# Node_Sensor_Lora_Sche.net
KiCad netlist of a schematic drawn in Altium Designer
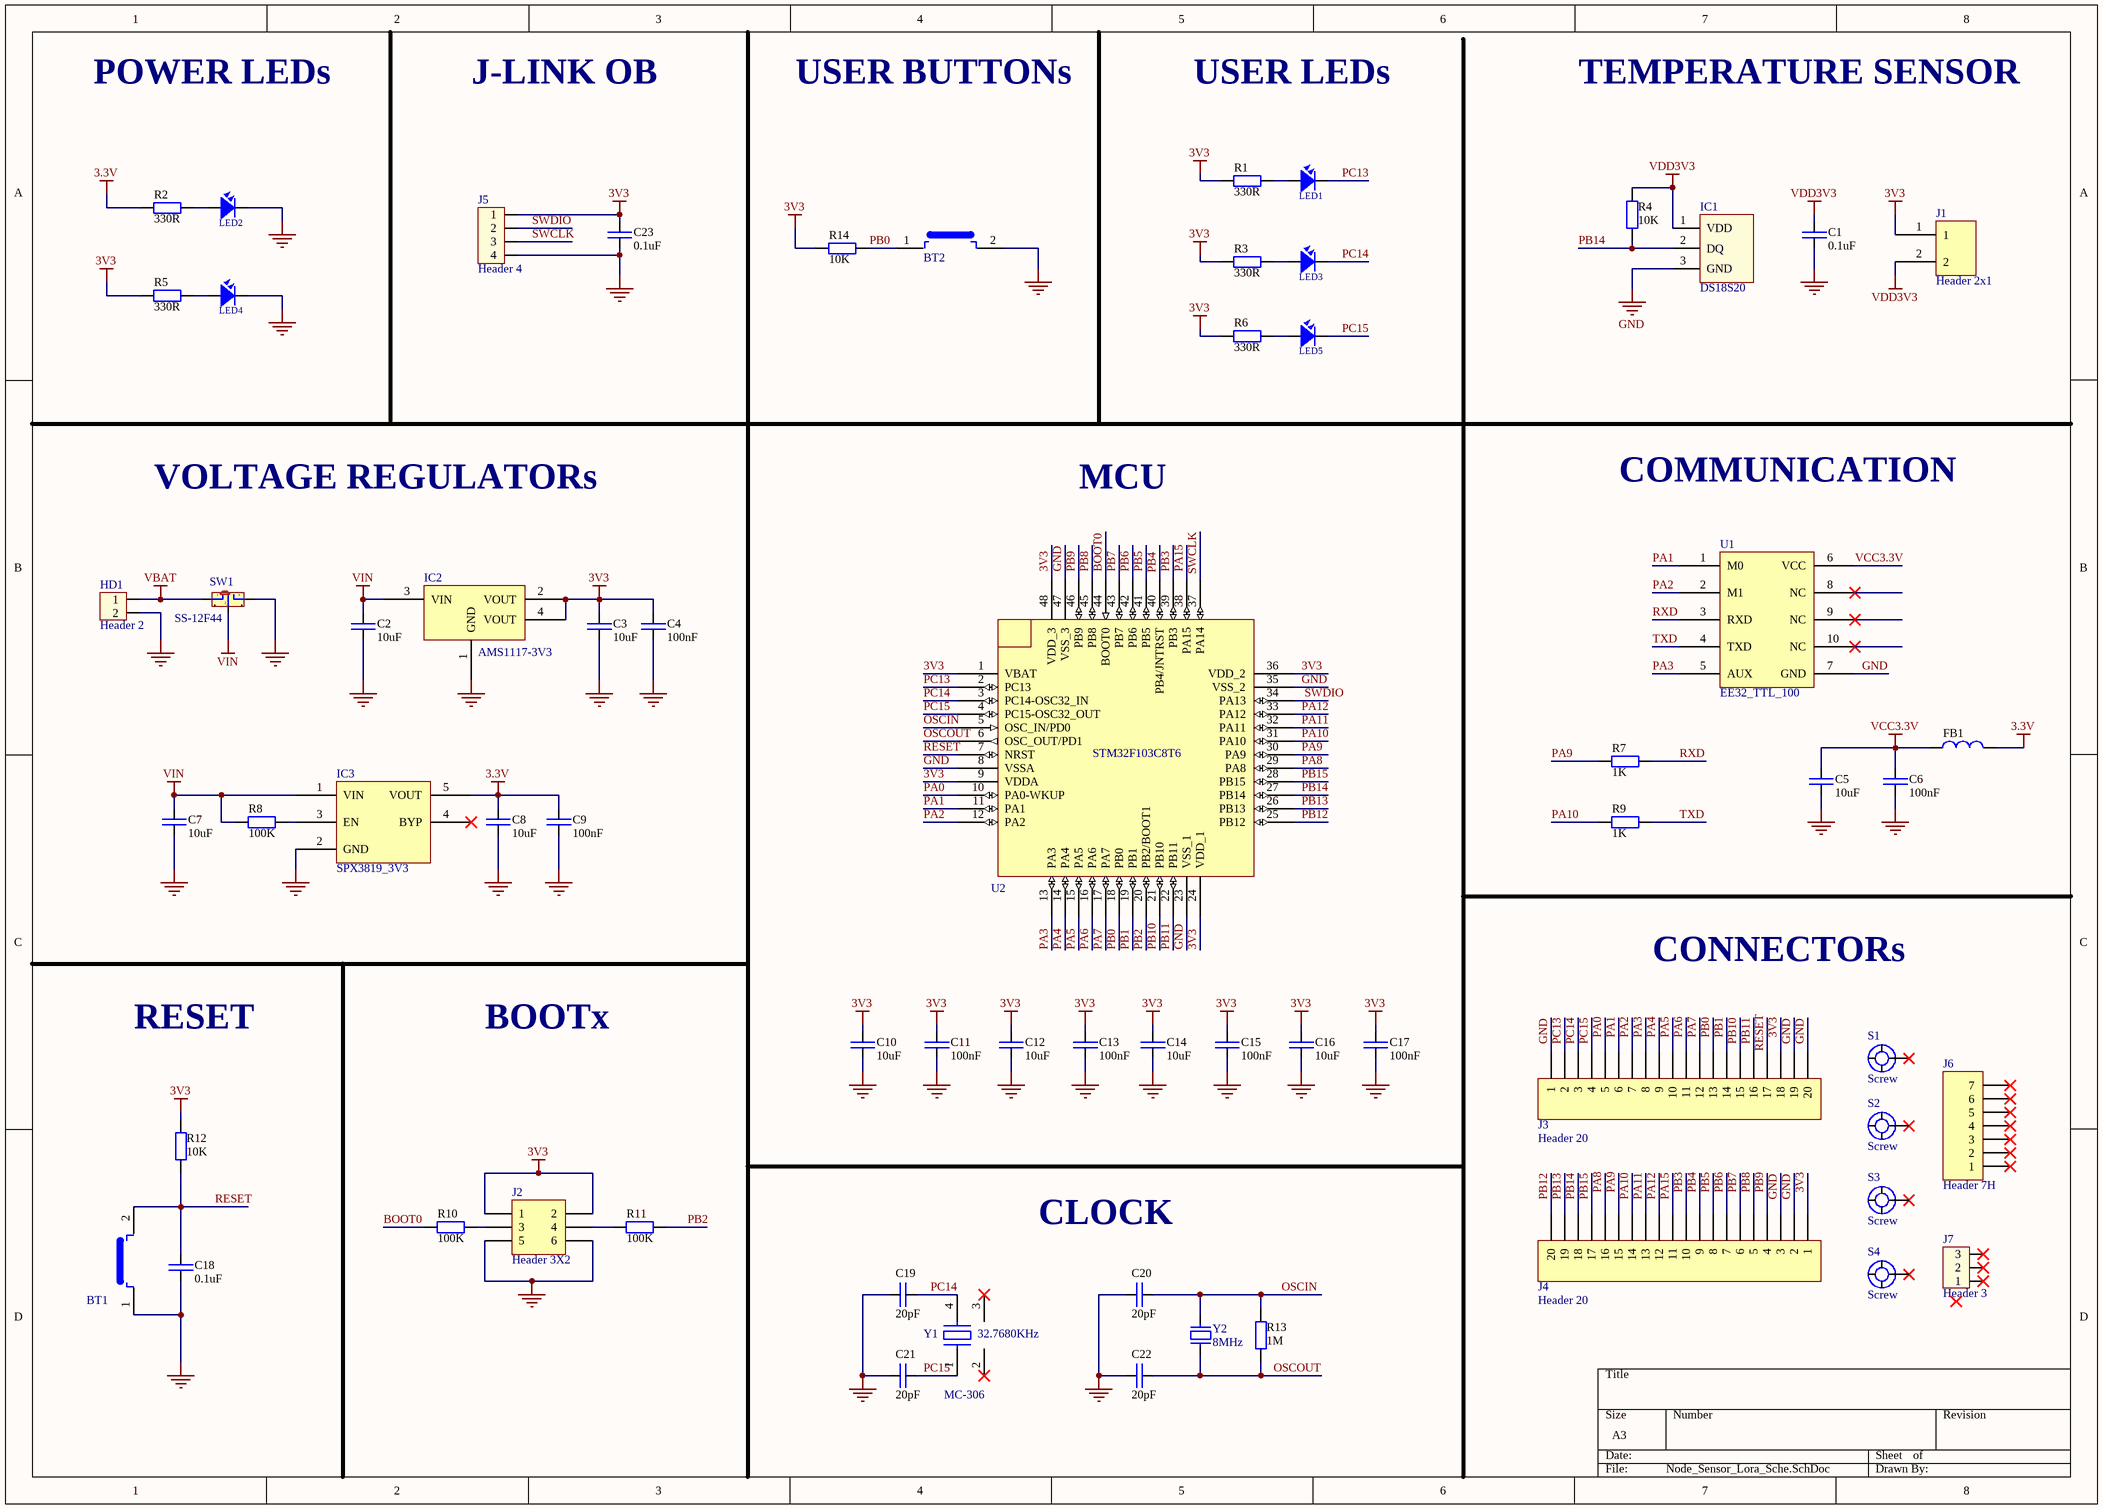
[diagram p0: Node_Sensor_Lora_Sche.SchDoc]

(export (version "E")
  (design (tool "Eeschema 10.0.6"))
  (components
    (comp (ref "BT1") (value "~") (footprint "SW4") (libsource (lib "my_Library") (part "BUTTON")))
    (comp (ref "BT2") (value "BT") (footprint "SW4") (libsource (lib "my_Library") (part "BUTTON")))
    (comp (ref "C1")
      (value "0.1uF")
      (footprint "CAPC2012X135N")
      (description "Capacitor SMD Cer 1.8nF 10% 50V X7R 0805")
      (fields (field (name "TOLERANCE") "±10%") (field (name "Comment") "approved sub OK"))
      (libsource (lib "my_Library") (part "CAP C_0805"))
    )
    (comp (ref "C2")
      (value "10uF")
      (footprint "CAPC2012X135N")
      (description "Capacitor SMD Cer 1.8nF 10% 50V X7R 0805")
      (fields (field (name "TOLERANCE") "±10%") (field (name "Comment") "approved sub OK"))
      (libsource (lib "my_Library") (part "CAP C_0805"))
    )
    (comp (ref "C3")
      (value "10uF")
      (footprint "CAPC2012X135N")
      (description "Capacitor SMD Cer 1.8nF 10% 50V X7R 0805")
      (fields (field (name "TOLERANCE") "±10%") (field (name "Comment") "approved sub OK"))
      (libsource (lib "my_Library") (part "CAP C_0805"))
    )
    (comp (ref "C4")
      (value "100nF")
      (footprint "CAPC2012X135N")
      (description "Capacitor SMD Cer 1.8nF 10% 50V X7R 0805")
      (fields (field (name "TOLERANCE") "±10%") (field (name "Comment") "approved sub OK"))
      (libsource (lib "my_Library") (part "CAP C_0805"))
    )
    (comp (ref "C5")
      (value "10uF")
      (footprint "CAPC2012X135N")
      (description "Capacitor SMD Cer 1.8nF 10% 50V X7R 0805")
      (fields (field (name "TOLERANCE") "±10%") (field (name "Comment") "approved sub OK"))
      (libsource (lib "my_Library") (part "CAP C_0805"))
    )
    (comp (ref "C6")
      (value "100nF")
      (footprint "CAPC2012X135N")
      (description "Capacitor SMD Cer 1.8nF 10% 50V X7R 0805")
      (fields (field (name "TOLERANCE") "±10%") (field (name "Comment") "approved sub OK"))
      (libsource (lib "my_Library") (part "CAP C_0805"))
    )
    (comp (ref "C7")
      (value "10uF")
      (footprint "CAPC2012X135N")
      (description "Capacitor SMD Cer 1.8nF 10% 50V X7R 0805")
      (fields (field (name "TOLERANCE") "±10%") (field (name "Comment") "approved sub OK"))
      (libsource (lib "my_Library") (part "CAP C_0805"))
    )
    (comp (ref "C8")
      (value "10uF")
      (footprint "CAPC2012X135N")
      (description "Capacitor SMD Cer 1.8nF 10% 50V X7R 0805")
      (fields (field (name "TOLERANCE") "±10%") (field (name "Comment") "approved sub OK"))
      (libsource (lib "my_Library") (part "CAP C_0805"))
    )
    (comp (ref "C9")
      (value "100nF")
      (footprint "CAPC2012X135N")
      (description "Capacitor SMD Cer 1.8nF 10% 50V X7R 0805")
      (fields (field (name "TOLERANCE") "±10%") (field (name "Comment") "approved sub OK"))
      (libsource (lib "my_Library") (part "CAP C_0805"))
    )
    (comp (ref "C10")
      (value "10uF")
      (footprint "CAPC2012X135N")
      (description "Capacitor SMD Cer 1.8nF 10% 50V X7R 0805")
      (fields (field (name "TOLERANCE") "±10%") (field (name "Comment") "approved sub OK"))
      (libsource (lib "my_Library") (part "CAP C_0805"))
    )
    (comp (ref "C11")
      (value "100nF")
      (footprint "CAPC2012X135N")
      (description "Capacitor SMD Cer 1.8nF 10% 50V X7R 0805")
      (fields (field (name "TOLERANCE") "±10%") (field (name "Comment") "approved sub OK"))
      (libsource (lib "my_Library") (part "CAP C_0805"))
    )
    (comp (ref "C12")
      (value "10uF")
      (footprint "CAPC2012X135N")
      (description "Capacitor SMD Cer 1.8nF 10% 50V X7R 0805")
      (fields (field (name "TOLERANCE") "±10%") (field (name "Comment") "approved sub OK"))
      (libsource (lib "my_Library") (part "CAP C_0805"))
    )
    (comp (ref "C13")
      (value "100nF")
      (footprint "CAPC2012X135N")
      (description "Capacitor SMD Cer 1.8nF 10% 50V X7R 0805")
      (fields (field (name "TOLERANCE") "±10%") (field (name "Comment") "approved sub OK"))
      (libsource (lib "my_Library") (part "CAP C_0805"))
    )
    (comp (ref "C14")
      (value "10uF")
      (footprint "CAPC2012X135N")
      (description "Capacitor SMD Cer 1.8nF 10% 50V X7R 0805")
      (fields (field (name "TOLERANCE") "±10%") (field (name "Comment") "approved sub OK"))
      (libsource (lib "my_Library") (part "CAP C_0805"))
    )
    (comp (ref "C15")
      (value "100nF")
      (footprint "CAPC2012X135N")
      (description "Capacitor SMD Cer 1.8nF 10% 50V X7R 0805")
      (fields (field (name "TOLERANCE") "±10%") (field (name "Comment") "approved sub OK"))
      (libsource (lib "my_Library") (part "CAP C_0805"))
    )
    (comp (ref "C16")
      (value "10uF")
      (footprint "CAPC2012X135N")
      (description "Capacitor SMD Cer 1.8nF 10% 50V X7R 0805")
      (fields (field (name "TOLERANCE") "±10%") (field (name "Comment") "approved sub OK"))
      (libsource (lib "my_Library") (part "CAP C_0805"))
    )
    (comp (ref "C17")
      (value "100nF")
      (footprint "CAPC2012X135N")
      (description "Capacitor SMD Cer 1.8nF 10% 50V X7R 0805")
      (fields (field (name "TOLERANCE") "±10%") (field (name "Comment") "approved sub OK"))
      (libsource (lib "my_Library") (part "CAP C_0805"))
    )
    (comp (ref "C18")
      (value "0.1uF")
      (footprint "CAPC2012X135N")
      (description "Capacitor SMD Cer 1.8nF 10% 50V X7R 0805")
      (fields (field (name "TOLERANCE") "±10%") (field (name "Comment") "approved sub OK"))
      (libsource (lib "my_Library") (part "CAP C_0805"))
    )
    (comp (ref "C19")
      (value "20pF")
      (footprint "CAPC2012X135N")
      (description "Capacitor SMD Cer 1.8nF 10% 50V X7R 0805")
      (fields (field (name "TOLERANCE") "±10%") (field (name "Comment") "approved sub OK"))
      (libsource (lib "my_Library") (part "CAP C_0805"))
    )
    (comp (ref "C20")
      (value "20pF")
      (footprint "CAPC2012X135N")
      (description "Capacitor SMD Cer 1.8nF 10% 50V X7R 0805")
      (fields (field (name "TOLERANCE") "±10%") (field (name "Comment") "approved sub OK"))
      (libsource (lib "my_Library") (part "CAP C_0805"))
    )
    (comp (ref "C21")
      (value "20pF")
      (footprint "CAPC2012X135N")
      (description "Capacitor SMD Cer 1.8nF 10% 50V X7R 0805")
      (fields (field (name "TOLERANCE") "±10%") (field (name "Comment") "approved sub OK"))
      (libsource (lib "my_Library") (part "CAP C_0805"))
    )
    (comp (ref "C22")
      (value "20pF")
      (footprint "CAPC2012X135N")
      (description "Capacitor SMD Cer 1.8nF 10% 50V X7R 0805")
      (fields (field (name "TOLERANCE") "±10%") (field (name "Comment") "approved sub OK"))
      (libsource (lib "my_Library") (part "CAP C_0805"))
    )
    (comp (ref "C23")
      (value "0.1uF")
      (footprint "CAPC2012X135N")
      (description "Capacitor SMD Cer 1.8nF 10% 50V X7R 0805")
      (fields (field (name "TOLERANCE") "±10%") (field (name "Comment") "approved sub OK"))
      (libsource (lib "my_Library") (part "CAP C_0805"))
    )
    (comp (ref "FB1")
      (value "2K2 @ 100 MHz")
      (footprint "FBC2012N")
      (description "Ferrite bead 2.2K Ohm at 100 MHz 200mA 0805 SMD")
      (libsource (lib "my_Library") (part "FERRITE_2K2-100MHz_0805"))
    )
    (comp (ref "HD1")
      (value "Header 2")
      (footprint "HED2")
      (description "Header 2 (Green)")
      (libsource (lib "my_Library") (part "Header 2"))
    )
    (comp (ref "IC1")
      (value "DS18S20")
      (footprint "DS18S20")
      (description "High Precision  1-Wire® Digital Thermometer")
      (libsource (lib "my_Library") (part "DS18S20"))
    )
    (comp (ref "IC2")
      (value "AMS1117-3V3")
      (footprint "SOT223")
      (description "SOT223, Fixed Voltage")
      (libsource (lib "my_Library") (part "AMS1117"))
    )
    (comp (ref "IC3")
      (value "SPX3819_3V3")
      (footprint "SOT23-5")
      (libsource (lib "my_Library") (part "SPX3819"))
    )
    (comp (ref "J1")
      (value "Header 2x1")
      (footprint "HDR_2x1")
      (libsource (lib "my_Library") (part "Header_2pins"))
    )
    (comp (ref "J2")
      (value "Header 3X2")
      (footprint "HDR2X3")
      (description "Header, 3-Pin, Dual row")
      (fields (field (name "PUBLISHER") "Altium Limited"))
      (libsource (lib "my_Library") (part "Header 3X2"))
    )
    (comp (ref "J3")
      (value "Header 20")
      (footprint "HDR1X20")
      (description "Header, 20-Pin")
      (fields (field (name "PUBLISHER") "Altium Limited"))
      (libsource (lib "my_Library") (part "Header 20"))
    )
    (comp (ref "J4")
      (value "Header 20")
      (footprint "HDR1X20")
      (description "Header, 20-Pin")
      (fields (field (name "PUBLISHER") "Altium Limited"))
      (libsource (lib "") (part "Header 20_1"))
    )
    (comp (ref "J5")
      (value "Header 4")
      (footprint "HDR _4PINS")
      (description "Header 4 (Green)")
      (libsource (lib "my_Library") (part "Header 4"))
    )
    (comp (ref "J6")
      (value "Header 7H")
      (footprint "CON7")
      (description "Header, 7-Pin, Right Angle")
      (fields (field (name "PUBLISHER") "Altium Limited"))
      (libsource (lib "my_Library") (part "Header 7H"))
    )
    (comp (ref "J7")
      (value "Header 3")
      (footprint "HED3")
      (description "Header 3 (Green)")
      (libsource (lib "my_Library") (part "Header 3"))
    )
    (comp (ref "LED1")
      (value "LED SMD")
      (footprint "SM-LED-0805-Blue")
      (libsource (lib "my_Library") (part "LED SMD 0805"))
    )
    (comp (ref "LED2")
      (value "LED SMD")
      (footprint "SM-LED-0805-Blue")
      (libsource (lib "my_Library") (part "LED SMD 0805"))
    )
    (comp (ref "LED3")
      (value "LED SMD")
      (footprint "SM-LED-0805-Blue")
      (libsource (lib "my_Library") (part "LED SMD 0805"))
    )
    (comp (ref "LED4")
      (value "LED SMD")
      (footprint "SM-LED-0805-Blue")
      (libsource (lib "my_Library") (part "LED SMD 0805"))
    )
    (comp (ref "LED5")
      (value "LED SMD")
      (footprint "SM-LED-0805-Blue")
      (libsource (lib "my_Library") (part "LED SMD 0805"))
    )
    (comp (ref "R1")
      (value "330R")
      (footprint "RESC2012N_ZERO")
      (description "Resistor SMD chip 0.0 Ohm 0.125W 0805")
      (fields (field (name "Comment") "100R"))
      (libsource (lib "my_Library") (part "RES_0805"))
    )
    (comp (ref "R2")
      (value "330R")
      (footprint "RESC2012N_ZERO")
      (description "Resistor SMD chip 0.0 Ohm 0.125W 0805")
      (libsource (lib "my_Library") (part "RES_0805"))
    )
    (comp (ref "R3")
      (value "330R")
      (footprint "RESC2012N_ZERO")
      (description "Resistor SMD chip 0.0 Ohm 0.125W 0805")
      (fields (field (name "Comment") "100R"))
      (libsource (lib "my_Library") (part "RES_0805"))
    )
    (comp (ref "R4")
      (value "10K")
      (footprint "RESC2012N_ZERO")
      (description "Resistor SMD chip 0.0 Ohm 0.125W 0805")
      (fields (field (name "Comment") "100R"))
      (libsource (lib "") (part "RES_0805_1"))
    )
    (comp (ref "R5")
      (value "330R")
      (footprint "RESC2012N_ZERO")
      (description "Resistor SMD chip 0.0 Ohm 0.125W 0805")
      (fields (field (name "Comment") "100R"))
      (libsource (lib "my_Library") (part "RES_0805"))
    )
    (comp (ref "R6")
      (value "330R")
      (footprint "RESC2012N_ZERO")
      (description "Resistor SMD chip 0.0 Ohm 0.125W 0805")
      (fields (field (name "Comment") "100R"))
      (libsource (lib "my_Library") (part "RES_0805"))
    )
    (comp (ref "R7")
      (value "1K")
      (footprint "RESC2012N_ZERO")
      (description "Resistor SMD chip 0.0 Ohm 0.125W 0805")
      (fields (field (name "Comment") "100R"))
      (libsource (lib "my_Library") (part "RES_0805"))
    )
    (comp (ref "R8")
      (value "100K")
      (footprint "RESC2012N_ZERO")
      (description "Resistor SMD chip 0.0 Ohm 0.125W 0805")
      (fields (field (name "Comment") "100R"))
      (libsource (lib "my_Library") (part "RES_0805"))
    )
    (comp (ref "R9")
      (value "1K")
      (footprint "RESC2012N_ZERO")
      (description "Resistor SMD chip 0.0 Ohm 0.125W 0805")
      (fields (field (name "Comment") "100R"))
      (libsource (lib "my_Library") (part "RES_0805"))
    )
    (comp (ref "R10")
      (value "100K")
      (footprint "RESC2012N_ZERO")
      (description "Resistor SMD chip 0.0 Ohm 0.125W 0805")
      (fields (field (name "Comment") "100R"))
      (libsource (lib "my_Library") (part "RES_0805"))
    )
    (comp (ref "R11")
      (value "100K")
      (footprint "RESC2012N_ZERO")
      (description "Resistor SMD chip 0.0 Ohm 0.125W 0805")
      (fields (field (name "Comment") "100R"))
      (libsource (lib "my_Library") (part "RES_0805"))
    )
    (comp (ref "R12")
      (value "10K")
      (footprint "RESC2012N_ZERO")
      (description "Resistor SMD chip 0.0 Ohm 0.125W 0805")
      (fields (field (name "Comment") "100R"))
      (libsource (lib "") (part "RES_0805_2"))
    )
    (comp (ref "R13")
      (value "1M")
      (footprint "RESC2012N_ZERO")
      (description "Resistor SMD chip 0.0 Ohm 0.125W 0805")
      (fields (field (name "Comment") "100R"))
      (libsource (lib "") (part "RES_0805_2"))
    )
    (comp (ref "R14")
      (value "10K")
      (footprint "RESC2012N_ZERO")
      (description "Resistor SMD chip 0.0 Ohm 0.125W 0805")
      (fields (field (name "Comment") "100R"))
      (libsource (lib "my_Library") (part "RES_0805"))
    )
    (comp (ref "S1") (value "Screw") (footprint "Screw 3 small") (libsource (lib "lpson") (part "Screw")))
    (comp (ref "S2") (value "Screw") (footprint "Screw 3 small") (libsource (lib "lpson") (part "Screw")))
    (comp (ref "S3") (value "Screw") (footprint "Screw 3 small") (libsource (lib "lpson") (part "Screw")))
    (comp (ref "S4") (value "Screw") (footprint "Screw 3 small") (libsource (lib "lpson") (part "Screw")))
    (comp (ref "SW1")
      (value "SS-12F44")
      (footprint "SW102")
      (description "Switch 102 on Broad")
      (libsource (lib "my_Library") (part "SW102A"))
    )
    (comp (ref "U1")
      (value "EE32_TTL_100")
      (footprint "E32_TTL_100")
      (libsource (lib "my_Library") (part "Module Lora E32_TTL_100"))
    )
    (comp (ref "U2")
      (value "STM32F103C8T6")
      (footprint "STM32_LQPF48")
      (description "STM32 ARM-based 32-bit MCU with 64 Kbytes Flash, 48-pin LQFP, Industrial Temperature")
      (fields (field (name "PUBLISHER") "Altium Limited"))
      (libsource (lib "my_Library") (part "STM32F103xx_LQFP48"))
    )
    (comp (ref "Y1")
      (value "32.7680KHz")
      (footprint "Epson_MC-306_32.7680K-A0-ROHS_0")
      (description "CRYSTAL 32.7680KHZ 12.5PF SMD")
      (fields
        (field (name "PART NUMBER") "MC-306")
        (field (name "MANUFACTURER") "Epson")
        (field (name "MOUSER PART NUMBER") "732-MC30632.7680KA0R")
      )
      (libsource (lib "Crys_Epson_MC-306_32.7680K-A0-ROHS_eec") (part "Crys_Epson_MC-306_32.7680K-A0-ROHS_eec"))
    )
    (comp (ref "Y2")
      (value "8MHz")
      (footprint "CRYSTAL")
      (description "Crystal For all Crystal 2pin.")
      (libsource (lib "my_Library") (part "CRYSTAL"))
    )
  )
  (nets
    (net (code "1") (name "/BOOT0") (class "Default")
      (node (ref "R10") (pin "1") (pinfunction "1_1") (pintype "passive"))
      (node (ref "U2") (pin "44") (pinfunction "BOOT0_44") (pintype "input"))
    )
    (net (code "2") (name "/OSCIN") (class "Default")
      (node (ref "C20") (pin "2") (pintype "passive"))
      (node (ref "R13") (pin "1") (pinfunction "1_1") (pintype "passive"))
      (node (ref "U2") (pin "5") (pinfunction "OSC_IN/PD0_5") (pintype "input"))
      (node (ref "Y2") (pin "2") (pinfunction "2_2") (pintype "passive"))
    )
    (net (code "3") (name "/OSCOUT") (class "Default")
      (node (ref "C22") (pin "2") (pintype "passive"))
      (node (ref "R13") (pin "2") (pinfunction "2_2") (pintype "passive"))
      (node (ref "U2") (pin "6") (pinfunction "OSC_OUT/PD1_6") (pintype "output"))
      (node (ref "Y2") (pin "1") (pinfunction "1_1") (pintype "passive"))
    )
    (net (code "4") (name "/PA0") (class "Default")
      (node (ref "J3") (pin "5") (pinfunction "5_5") (pintype "passive"))
      (node (ref "U2") (pin "10") (pinfunction "PA0-WKUP_10") (pintype "bidirectional"))
    )
    (net (code "5") (name "/PA1") (class "Default")
      (node (ref "J3") (pin "6") (pinfunction "6_6") (pintype "passive"))
      (node (ref "U1") (pin "1") (pinfunction "M0_1") (pintype "passive"))
      (node (ref "U2") (pin "11") (pinfunction "PA1_11") (pintype "bidirectional"))
    )
    (net (code "6") (name "/PA2") (class "Default")
      (node (ref "J3") (pin "7") (pinfunction "7_7") (pintype "passive"))
      (node (ref "U1") (pin "2") (pinfunction "M1_2") (pintype "passive"))
      (node (ref "U2") (pin "12") (pinfunction "PA2_12") (pintype "bidirectional"))
    )
    (net (code "7") (name "/PA3") (class "Default")
      (node (ref "J3") (pin "8") (pinfunction "8_8") (pintype "passive"))
      (node (ref "U1") (pin "5") (pinfunction "AUX_5") (pintype "passive"))
      (node (ref "U2") (pin "13") (pinfunction "PA3_13") (pintype "bidirectional"))
    )
    (net (code "8") (name "/PA4") (class "Default")
      (node (ref "J3") (pin "9") (pinfunction "9_9") (pintype "passive"))
      (node (ref "U2") (pin "14") (pinfunction "PA4_14") (pintype "bidirectional"))
    )
    (net (code "9") (name "/PA5") (class "Default")
      (node (ref "J3") (pin "10") (pinfunction "10_10") (pintype "passive"))
      (node (ref "U2") (pin "15") (pinfunction "PA5_15") (pintype "bidirectional"))
    )
    (net (code "10") (name "/PA6") (class "Default")
      (node (ref "J3") (pin "11") (pinfunction "11_11") (pintype "passive"))
      (node (ref "U2") (pin "16") (pinfunction "PA6_16") (pintype "bidirectional"))
    )
    (net (code "11") (name "/PA7") (class "Default")
      (node (ref "J3") (pin "12") (pinfunction "12_12") (pintype "passive"))
      (node (ref "U2") (pin "17") (pinfunction "PA7_17") (pintype "bidirectional"))
    )
    (net (code "12") (name "/PA8") (class "Default")
      (node (ref "J4") (pin "16") (pinfunction "16_16") (pintype "passive"))
      (node (ref "U2") (pin "29") (pinfunction "PA8_29") (pintype "bidirectional"))
    )
    (net (code "13") (name "/PA9") (class "Default")
      (node (ref "J4") (pin "15") (pinfunction "15_15") (pintype "passive"))
      (node (ref "R7") (pin "1") (pinfunction "1_1") (pintype "passive"))
      (node (ref "U2") (pin "30") (pinfunction "PA9_30") (pintype "bidirectional"))
    )
    (net (code "14") (name "/PA10") (class "Default")
      (node (ref "J4") (pin "14") (pinfunction "14_14") (pintype "passive"))
      (node (ref "R9") (pin "1") (pinfunction "1_1") (pintype "passive"))
      (node (ref "U2") (pin "31") (pinfunction "PA10_31") (pintype "bidirectional"))
    )
    (net (code "15") (name "/PA11") (class "Default")
      (node (ref "J4") (pin "13") (pinfunction "13_13") (pintype "passive"))
      (node (ref "U2") (pin "32") (pinfunction "PA11_32") (pintype "bidirectional"))
    )
    (net (code "16") (name "/PA12") (class "Default")
      (node (ref "J4") (pin "12") (pinfunction "12_12") (pintype "passive"))
      (node (ref "U2") (pin "33") (pinfunction "PA12_33") (pintype "bidirectional"))
    )
    (net (code "17") (name "/PA15") (class "Default")
      (node (ref "J4") (pin "11") (pinfunction "11_11") (pintype "passive"))
      (node (ref "U2") (pin "38") (pinfunction "PA15_38") (pintype "bidirectional"))
    )
    (net (code "18") (name "/PB0") (class "Default")
      (node (ref "BT2") (pin "1") (pinfunction "1_1") (pintype "passive"))
      (node (ref "J3") (pin "13") (pinfunction "13_13") (pintype "passive"))
      (node (ref "R14") (pin "2") (pinfunction "2_2") (pintype "passive"))
      (node (ref "U2") (pin "18") (pinfunction "PB0_18") (pintype "bidirectional"))
    )
    (net (code "19") (name "/PB1") (class "Default")
      (node (ref "J3") (pin "14") (pinfunction "14_14") (pintype "passive"))
      (node (ref "U2") (pin "19") (pinfunction "PB1_19") (pintype "bidirectional"))
    )
    (net (code "20") (name "/PB2") (class "Default")
      (node (ref "R11") (pin "2") (pinfunction "2_2") (pintype "passive"))
      (node (ref "U2") (pin "20") (pinfunction "PB2/BOOT1_20") (pintype "bidirectional"))
    )
    (net (code "21") (name "/PB3") (class "Default")
      (node (ref "J4") (pin "10") (pinfunction "10_10") (pintype "passive"))
      (node (ref "U2") (pin "39") (pinfunction "PB3_39") (pintype "bidirectional"))
    )
    (net (code "22") (name "/PB4") (class "Default")
      (node (ref "J4") (pin "9") (pinfunction "9_9") (pintype "passive"))
      (node (ref "U2") (pin "40") (pinfunction "PB4/JNTRST_40") (pintype "bidirectional"))
    )
    (net (code "23") (name "/PB5") (class "Default")
      (node (ref "J4") (pin "8") (pinfunction "8_8") (pintype "passive"))
      (node (ref "U2") (pin "41") (pinfunction "PB5_41") (pintype "bidirectional"))
    )
    (net (code "24") (name "/PB6") (class "Default")
      (node (ref "J4") (pin "7") (pinfunction "7_7") (pintype "passive"))
      (node (ref "U2") (pin "42") (pinfunction "PB6_42") (pintype "bidirectional"))
    )
    (net (code "25") (name "/PB7") (class "Default")
      (node (ref "J4") (pin "6") (pinfunction "6_6") (pintype "passive"))
      (node (ref "U2") (pin "43") (pinfunction "PB7_43") (pintype "bidirectional"))
    )
    (net (code "26") (name "/PB8") (class "Default")
      (node (ref "J4") (pin "5") (pinfunction "5_5") (pintype "passive"))
      (node (ref "U2") (pin "45") (pinfunction "PB8_45") (pintype "bidirectional"))
    )
    (net (code "27") (name "/PB9") (class "Default")
      (node (ref "J4") (pin "4") (pinfunction "4_4") (pintype "passive"))
      (node (ref "U2") (pin "46") (pinfunction "PB9_46") (pintype "bidirectional"))
    )
    (net (code "28") (name "/PB10") (class "Default")
      (node (ref "J3") (pin "15") (pinfunction "15_15") (pintype "passive"))
      (node (ref "U2") (pin "21") (pinfunction "PB10_21") (pintype "bidirectional"))
    )
    (net (code "29") (name "/PB11") (class "Default")
      (node (ref "J3") (pin "16") (pinfunction "16_16") (pintype "passive"))
      (node (ref "U2") (pin "22") (pinfunction "PB11_22") (pintype "bidirectional"))
    )
    (net (code "30") (name "/PB12") (class "Default")
      (node (ref "J4") (pin "20") (pinfunction "20_20") (pintype "passive"))
      (node (ref "U2") (pin "25") (pinfunction "PB12_25") (pintype "bidirectional"))
    )
    (net (code "31") (name "/PB13") (class "Default")
      (node (ref "J4") (pin "19") (pinfunction "19_19") (pintype "passive"))
      (node (ref "U2") (pin "26") (pinfunction "PB13_26") (pintype "bidirectional"))
    )
    (net (code "32") (name "/PB14") (class "Default")
      (node (ref "IC1") (pin "2") (pinfunction "DQ_2") (pintype "passive"))
      (node (ref "J4") (pin "18") (pinfunction "18_18") (pintype "passive"))
      (node (ref "R4") (pin "1") (pinfunction "1_1") (pintype "passive"))
      (node (ref "U2") (pin "27") (pinfunction "PB14_27") (pintype "bidirectional"))
    )
    (net (code "33") (name "/PB15") (class "Default")
      (node (ref "J4") (pin "17") (pinfunction "17_17") (pintype "passive"))
      (node (ref "U2") (pin "28") (pinfunction "PB15_28") (pintype "bidirectional"))
    )
    (net (code "34") (name "/PC13") (class "Default")
      (node (ref "J3") (pin "2") (pinfunction "2_2") (pintype "passive"))
      (node (ref "LED1") (pin "2") (pinfunction "2_2") (pintype "passive"))
      (node (ref "U2") (pin "2") (pinfunction "PC13_2") (pintype "bidirectional"))
    )
    (net (code "35") (name "/PC14") (class "Default")
      (node (ref "C19") (pin "2") (pintype "passive"))
      (node (ref "J3") (pin "3") (pinfunction "3_3") (pintype "passive"))
      (node (ref "LED3") (pin "2") (pinfunction "2_2") (pintype "passive"))
      (node (ref "U2") (pin "3") (pinfunction "PC14-OSC32_IN_3") (pintype "bidirectional"))
      (node (ref "Y1") (pin "4") (pinfunction "4_4") (pintype "passive"))
    )
    (net (code "36") (name "/PC15") (class "Default")
      (node (ref "C21") (pin "2") (pintype "passive"))
      (node (ref "J3") (pin "4") (pinfunction "4_4") (pintype "passive"))
      (node (ref "LED5") (pin "2") (pinfunction "2_2") (pintype "passive"))
      (node (ref "U2") (pin "4") (pinfunction "PC15-OSC32_OUT_4") (pintype "bidirectional"))
      (node (ref "Y1") (pin "1") (pinfunction "1_1") (pintype "passive"))
    )
    (net (code "37") (name "/RESET") (class "Default")
      (node (ref "BT1") (pin "2") (pinfunction "2_2") (pintype "passive"))
      (node (ref "C18") (pin "1") (pintype "passive"))
      (node (ref "J3") (pin "17") (pinfunction "17_17") (pintype "passive"))
      (node (ref "R12") (pin "2") (pinfunction "2_2") (pintype "passive"))
      (node (ref "U2") (pin "7") (pinfunction "NRST_7") (pintype "bidirectional"))
    )
    (net (code "38") (name "/RXD") (class "Default")
      (node (ref "R7") (pin "2") (pinfunction "2_2") (pintype "passive"))
      (node (ref "U1") (pin "3") (pinfunction "RXD_3") (pintype "passive"))
    )
    (net (code "39") (name "/SWCLK") (class "Default")
      (node (ref "J5") (pin "3") (pinfunction "3_3") (pintype "passive"))
      (node (ref "U2") (pin "37") (pinfunction "PA14_37") (pintype "bidirectional"))
    )
    (net (code "40") (name "/SWDIO") (class "Default")
      (node (ref "J5") (pin "2") (pinfunction "2_2") (pintype "passive"))
      (node (ref "U2") (pin "34") (pinfunction "PA13_34") (pintype "bidirectional"))
    )
    (net (code "41") (name "/TXD") (class "Default")
      (node (ref "R9") (pin "2") (pinfunction "2_2") (pintype "passive"))
      (node (ref "U1") (pin "4") (pinfunction "TXD_4") (pintype "passive"))
    )
    (net (code "42") (name "3.3V") (class "Default")
      (node (ref "C8") (pin "1") (pintype "passive"))
      (node (ref "C9") (pin "1") (pintype "passive"))
      (node (ref "FB1") (pin "2") (pinfunction "2_2") (pintype "passive"))
      (node (ref "IC3") (pin "5") (pinfunction "VOUT_5") (pintype "passive"))
      (node (ref "R2") (pin "1") (pinfunction "1_1") (pintype "passive"))
    )
    (net (code "43") (name "3V3") (class "Default")
      (node (ref "C10") (pin "1") (pintype "passive"))
      (node (ref "C11") (pin "1") (pintype "passive"))
      (node (ref "C12") (pin "1") (pintype "passive"))
      (node (ref "C13") (pin "1") (pintype "passive"))
      (node (ref "C14") (pin "1") (pintype "passive"))
      (node (ref "C15") (pin "1") (pintype "passive"))
      (node (ref "C16") (pin "1") (pintype "passive"))
      (node (ref "C17") (pin "1") (pintype "passive"))
      (node (ref "C23") (pin "1") (pintype "passive"))
      (node (ref "C3") (pin "1") (pintype "passive"))
      (node (ref "C4") (pin "1") (pintype "passive"))
      (node (ref "IC2") (pin "2") (pinfunction "VOUT_2") (pintype "passive"))
      (node (ref "IC2") (pin "4") (pinfunction "VOUT_4") (pintype "passive"))
      (node (ref "J1") (pin "1") (pinfunction "1_1") (pintype "passive"))
      (node (ref "J2") (pin "1") (pinfunction "1_1") (pintype "passive"))
      (node (ref "J2") (pin "2") (pinfunction "2_2") (pintype "passive"))
      (node (ref "J3") (pin "18") (pinfunction "18_18") (pintype "passive"))
      (node (ref "J4") (pin "1") (pinfunction "1_1") (pintype "passive"))
      (node (ref "J5") (pin "1") (pinfunction "1_1") (pintype "passive"))
      (node (ref "R1") (pin "1") (pinfunction "1_1") (pintype "passive"))
      (node (ref "R12") (pin "1") (pinfunction "1_1") (pintype "passive"))
      (node (ref "R14") (pin "1") (pinfunction "1_1") (pintype "passive"))
      (node (ref "R3") (pin "1") (pinfunction "1_1") (pintype "passive"))
      (node (ref "R5") (pin "1") (pinfunction "1_1") (pintype "passive"))
      (node (ref "R6") (pin "1") (pinfunction "1_1") (pintype "passive"))
      (node (ref "U2") (pin "1") (pinfunction "VBAT_1") (pintype "power_in"))
      (node (ref "U2") (pin "24") (pinfunction "VDD_1_24") (pintype "power_in"))
      (node (ref "U2") (pin "36") (pinfunction "VDD_2_36") (pintype "power_in"))
      (node (ref "U2") (pin "48") (pinfunction "VDD_3_48") (pintype "power_in"))
      (node (ref "U2") (pin "9") (pinfunction "VDDA_9") (pintype "power_in"))
    )
    (net (code "44") (name "GND") (class "Default")
      (node (ref "BT1") (pin "1") (pinfunction "1_1") (pintype "passive"))
      (node (ref "BT2") (pin "2") (pinfunction "2_2") (pintype "passive"))
      (node (ref "C1") (pin "1") (pintype "passive"))
      (node (ref "C10") (pin "2") (pintype "passive"))
      (node (ref "C11") (pin "2") (pintype "passive"))
      (node (ref "C12") (pin "2") (pintype "passive"))
      (node (ref "C13") (pin "2") (pintype "passive"))
      (node (ref "C14") (pin "2") (pintype "passive"))
      (node (ref "C15") (pin "2") (pintype "passive"))
      (node (ref "C16") (pin "2") (pintype "passive"))
      (node (ref "C17") (pin "2") (pintype "passive"))
      (node (ref "C18") (pin "2") (pintype "passive"))
      (node (ref "C19") (pin "1") (pintype "passive"))
      (node (ref "C2") (pin "2") (pintype "passive"))
      (node (ref "C20") (pin "1") (pintype "passive"))
      (node (ref "C21") (pin "1") (pintype "passive"))
      (node (ref "C22") (pin "1") (pintype "passive"))
      (node (ref "C23") (pin "2") (pintype "passive"))
      (node (ref "C3") (pin "2") (pintype "passive"))
      (node (ref "C4") (pin "2") (pintype "passive"))
      (node (ref "C5") (pin "2") (pintype "passive"))
      (node (ref "C6") (pin "2") (pintype "passive"))
      (node (ref "C7") (pin "2") (pintype "passive"))
      (node (ref "C8") (pin "2") (pintype "passive"))
      (node (ref "C9") (pin "2") (pintype "passive"))
      (node (ref "HD1") (pin "2") (pinfunction "2_2") (pintype "passive"))
      (node (ref "IC1") (pin "3") (pinfunction "GND_3") (pintype "passive"))
      (node (ref "IC2") (pin "1") (pinfunction "GND_1") (pintype "passive"))
      (node (ref "IC3") (pin "2") (pinfunction "GND_2") (pintype "passive"))
      (node (ref "J2") (pin "5") (pinfunction "5_5") (pintype "passive"))
      (node (ref "J2") (pin "6") (pinfunction "6_6") (pintype "passive"))
      (node (ref "J3") (pin "1") (pinfunction "1_1") (pintype "passive"))
      (node (ref "J3") (pin "19") (pinfunction "19_19") (pintype "passive"))
      (node (ref "J3") (pin "20") (pinfunction "20_20") (pintype "passive"))
      (node (ref "J4") (pin "2") (pinfunction "2_2") (pintype "passive"))
      (node (ref "J4") (pin "3") (pinfunction "3_3") (pintype "passive"))
      (node (ref "J5") (pin "4") (pinfunction "4_4") (pintype "passive"))
      (node (ref "LED2") (pin "2") (pinfunction "2_2") (pintype "passive"))
      (node (ref "LED4") (pin "2") (pinfunction "2_2") (pintype "passive"))
      (node (ref "SW1") (pin "3") (pinfunction "3_3") (pintype "passive"))
      (node (ref "U1") (pin "7") (pinfunction "GND_7") (pintype "passive"))
      (node (ref "U2") (pin "23") (pinfunction "VSS_1_23") (pintype "power_in"))
      (node (ref "U2") (pin "35") (pinfunction "VSS_2_35") (pintype "power_in"))
      (node (ref "U2") (pin "47") (pinfunction "VSS_3_47") (pintype "power_in"))
      (node (ref "U2") (pin "8") (pinfunction "VSSA_8") (pintype "power_in"))
    )
    (net (code "45") (name "Net-(IC3-EN)") (class "Default")
      (node (ref "IC3") (pin "3") (pinfunction "EN_3") (pintype "passive"))
      (node (ref "R8") (pin "2") (pinfunction "2_2") (pintype "passive"))
    )
    (net (code "46") (name "Net-(J2-Pad3)") (class "Default")
      (node (ref "J2") (pin "3") (pinfunction "3_3") (pintype "passive"))
      (node (ref "R10") (pin "2") (pinfunction "2_2") (pintype "passive"))
    )
    (net (code "47") (name "Net-(J2-Pad4)") (class "Default")
      (node (ref "J2") (pin "4") (pinfunction "4_4") (pintype "passive"))
      (node (ref "R11") (pin "1") (pinfunction "1_1") (pintype "passive"))
    )
    (net (code "48") (name "Net-(LED1-Pad1)") (class "Default")
      (node (ref "LED1") (pin "1") (pinfunction "1_1") (pintype "passive"))
      (node (ref "R1") (pin "2") (pinfunction "2_2") (pintype "passive"))
    )
    (net (code "49") (name "Net-(LED2-Pad1)") (class "Default")
      (node (ref "LED2") (pin "1") (pinfunction "1_1") (pintype "passive"))
      (node (ref "R2") (pin "2") (pinfunction "2_2") (pintype "passive"))
    )
    (net (code "50") (name "Net-(LED3-Pad1)") (class "Default")
      (node (ref "LED3") (pin "1") (pinfunction "1_1") (pintype "passive"))
      (node (ref "R3") (pin "2") (pinfunction "2_2") (pintype "passive"))
    )
    (net (code "51") (name "Net-(LED4-Pad1)") (class "Default")
      (node (ref "LED4") (pin "1") (pinfunction "1_1") (pintype "passive"))
      (node (ref "R5") (pin "2") (pinfunction "2_2") (pintype "passive"))
    )
    (net (code "52") (name "Net-(LED5-Pad1)") (class "Default")
      (node (ref "LED5") (pin "1") (pinfunction "1_1") (pintype "passive"))
      (node (ref "R6") (pin "2") (pinfunction "2_2") (pintype "passive"))
    )
    (net (code "53") (name "VBAT") (class "Default")
      (node (ref "HD1") (pin "1") (pinfunction "1_1") (pintype "passive"))
      (node (ref "SW1") (pin "1") (pinfunction "1_1") (pintype "passive"))
    )
    (net (code "54") (name "VCC3.3V") (class "Default")
      (node (ref "C5") (pin "1") (pintype "passive"))
      (node (ref "C6") (pin "1") (pintype "passive"))
      (node (ref "FB1") (pin "1") (pinfunction "1_1") (pintype "passive"))
      (node (ref "U1") (pin "6") (pinfunction "VCC_6") (pintype "passive"))
    )
    (net (code "55") (name "VDD3V3") (class "Default")
      (node (ref "C1") (pin "2") (pintype "passive"))
      (node (ref "IC1") (pin "1") (pinfunction "VDD_1") (pintype "passive"))
      (node (ref "J1") (pin "2") (pinfunction "2_2") (pintype "passive"))
      (node (ref "R4") (pin "2") (pinfunction "2_2") (pintype "passive"))
    )
    (net (code "56") (name "VIN") (class "Default")
      (node (ref "C2") (pin "1") (pintype "passive"))
      (node (ref "C7") (pin "1") (pintype "passive"))
      (node (ref "IC2") (pin "3") (pinfunction "VIN_3") (pintype "passive"))
      (node (ref "IC3") (pin "1") (pinfunction "VIN_1") (pintype "passive"))
      (node (ref "R8") (pin "1") (pinfunction "1_1") (pintype "passive"))
      (node (ref "SW1") (pin "2") (pinfunction "2_2") (pintype "passive"))
    )
    (net (code "57") (name "unconnected-(IC3-BYP-Pad4)") (class "Default")
      (node (ref "IC3") (pin "4") (pinfunction "BYP_4") (pintype "passive+no_connect"))
    )
    (net (code "58") (name "unconnected-(J6-Pad1)") (class "Default")
      (node (ref "J6") (pin "1") (pinfunction "1_1") (pintype "passive+no_connect"))
    )
    (net (code "59") (name "unconnected-(J6-Pad2)") (class "Default")
      (node (ref "J6") (pin "2") (pinfunction "2_2") (pintype "passive+no_connect"))
    )
    (net (code "60") (name "unconnected-(J6-Pad3)") (class "Default")
      (node (ref "J6") (pin "3") (pinfunction "3_3") (pintype "passive+no_connect"))
    )
    (net (code "61") (name "unconnected-(J6-Pad4)") (class "Default")
      (node (ref "J6") (pin "4") (pinfunction "4_4") (pintype "passive+no_connect"))
    )
    (net (code "62") (name "unconnected-(J6-Pad5)") (class "Default")
      (node (ref "J6") (pin "5") (pinfunction "5_5") (pintype "passive+no_connect"))
    )
    (net (code "63") (name "unconnected-(J6-Pad6)") (class "Default")
      (node (ref "J6") (pin "6") (pinfunction "6_6") (pintype "passive+no_connect"))
    )
    (net (code "64") (name "unconnected-(J6-Pad7)") (class "Default")
      (node (ref "J6") (pin "7") (pinfunction "7_7") (pintype "passive+no_connect"))
    )
    (net (code "65") (name "unconnected-(J7-Pad1)") (class "Default")
      (node (ref "J7") (pin "1") (pinfunction "1_1") (pintype "passive+no_connect"))
    )
    (net (code "66") (name "unconnected-(J7-Pad2)") (class "Default")
      (node (ref "J7") (pin "2") (pinfunction "2_2") (pintype "passive+no_connect"))
    )
    (net (code "67") (name "unconnected-(J7-Pad3)") (class "Default")
      (node (ref "J7") (pin "3") (pinfunction "3_3") (pintype "passive+no_connect"))
    )
    (net (code "68") (name "unconnected-(S1-Pad1)") (class "Default")
      (node (ref "S1") (pin "1") (pinfunction "1_1") (pintype "passive+no_connect"))
    )
    (net (code "69") (name "unconnected-(S2-Pad1)") (class "Default")
      (node (ref "S2") (pin "1") (pinfunction "1_1") (pintype "passive+no_connect"))
    )
    (net (code "70") (name "unconnected-(S3-Pad1)") (class "Default")
      (node (ref "S3") (pin "1") (pinfunction "1_1") (pintype "passive+no_connect"))
    )
    (net (code "71") (name "unconnected-(S4-Pad1)") (class "Default")
      (node (ref "S4") (pin "1") (pinfunction "1_1") (pintype "passive+no_connect"))
    )
    (net (code "72") (name "unconnected-(SW1-Pad4)") (class "Default")
      (node (ref "SW1") (pin "4") (pinfunction "4_4") (pintype "passive"))
    )
    (net (code "73") (name "unconnected-(SW1-Pad5)") (class "Default")
      (node (ref "SW1") (pin "5") (pinfunction "5_5") (pintype "passive"))
    )
    (net (code "74") (name "unconnected-(U1-NC-Pad8)") (class "Default")
      (node (ref "U1") (pin "8") (pinfunction "NC_8") (pintype "passive+no_connect"))
    )
    (net (code "75") (name "unconnected-(U1-NC-Pad9)") (class "Default")
      (node (ref "U1") (pin "9") (pinfunction "NC_9") (pintype "passive+no_connect"))
    )
    (net (code "76") (name "unconnected-(U1-NC-Pad10)") (class "Default")
      (node (ref "U1") (pin "10") (pinfunction "NC_10") (pintype "passive+no_connect"))
    )
    (net (code "77") (name "unconnected-(Y1-NC-Pad2)") (class "Default")
      (node (ref "Y1") (pin "2") (pinfunction "NC_2") (pintype "passive+no_connect"))
    )
    (net (code "78") (name "unconnected-(Y1-NC-Pad3)") (class "Default")
      (node (ref "Y1") (pin "3") (pinfunction "NC_3") (pintype "passive+no_connect"))
    )
  )
)
